# Main.net
KiCad netlist of a schematic drawn in Altium Designer
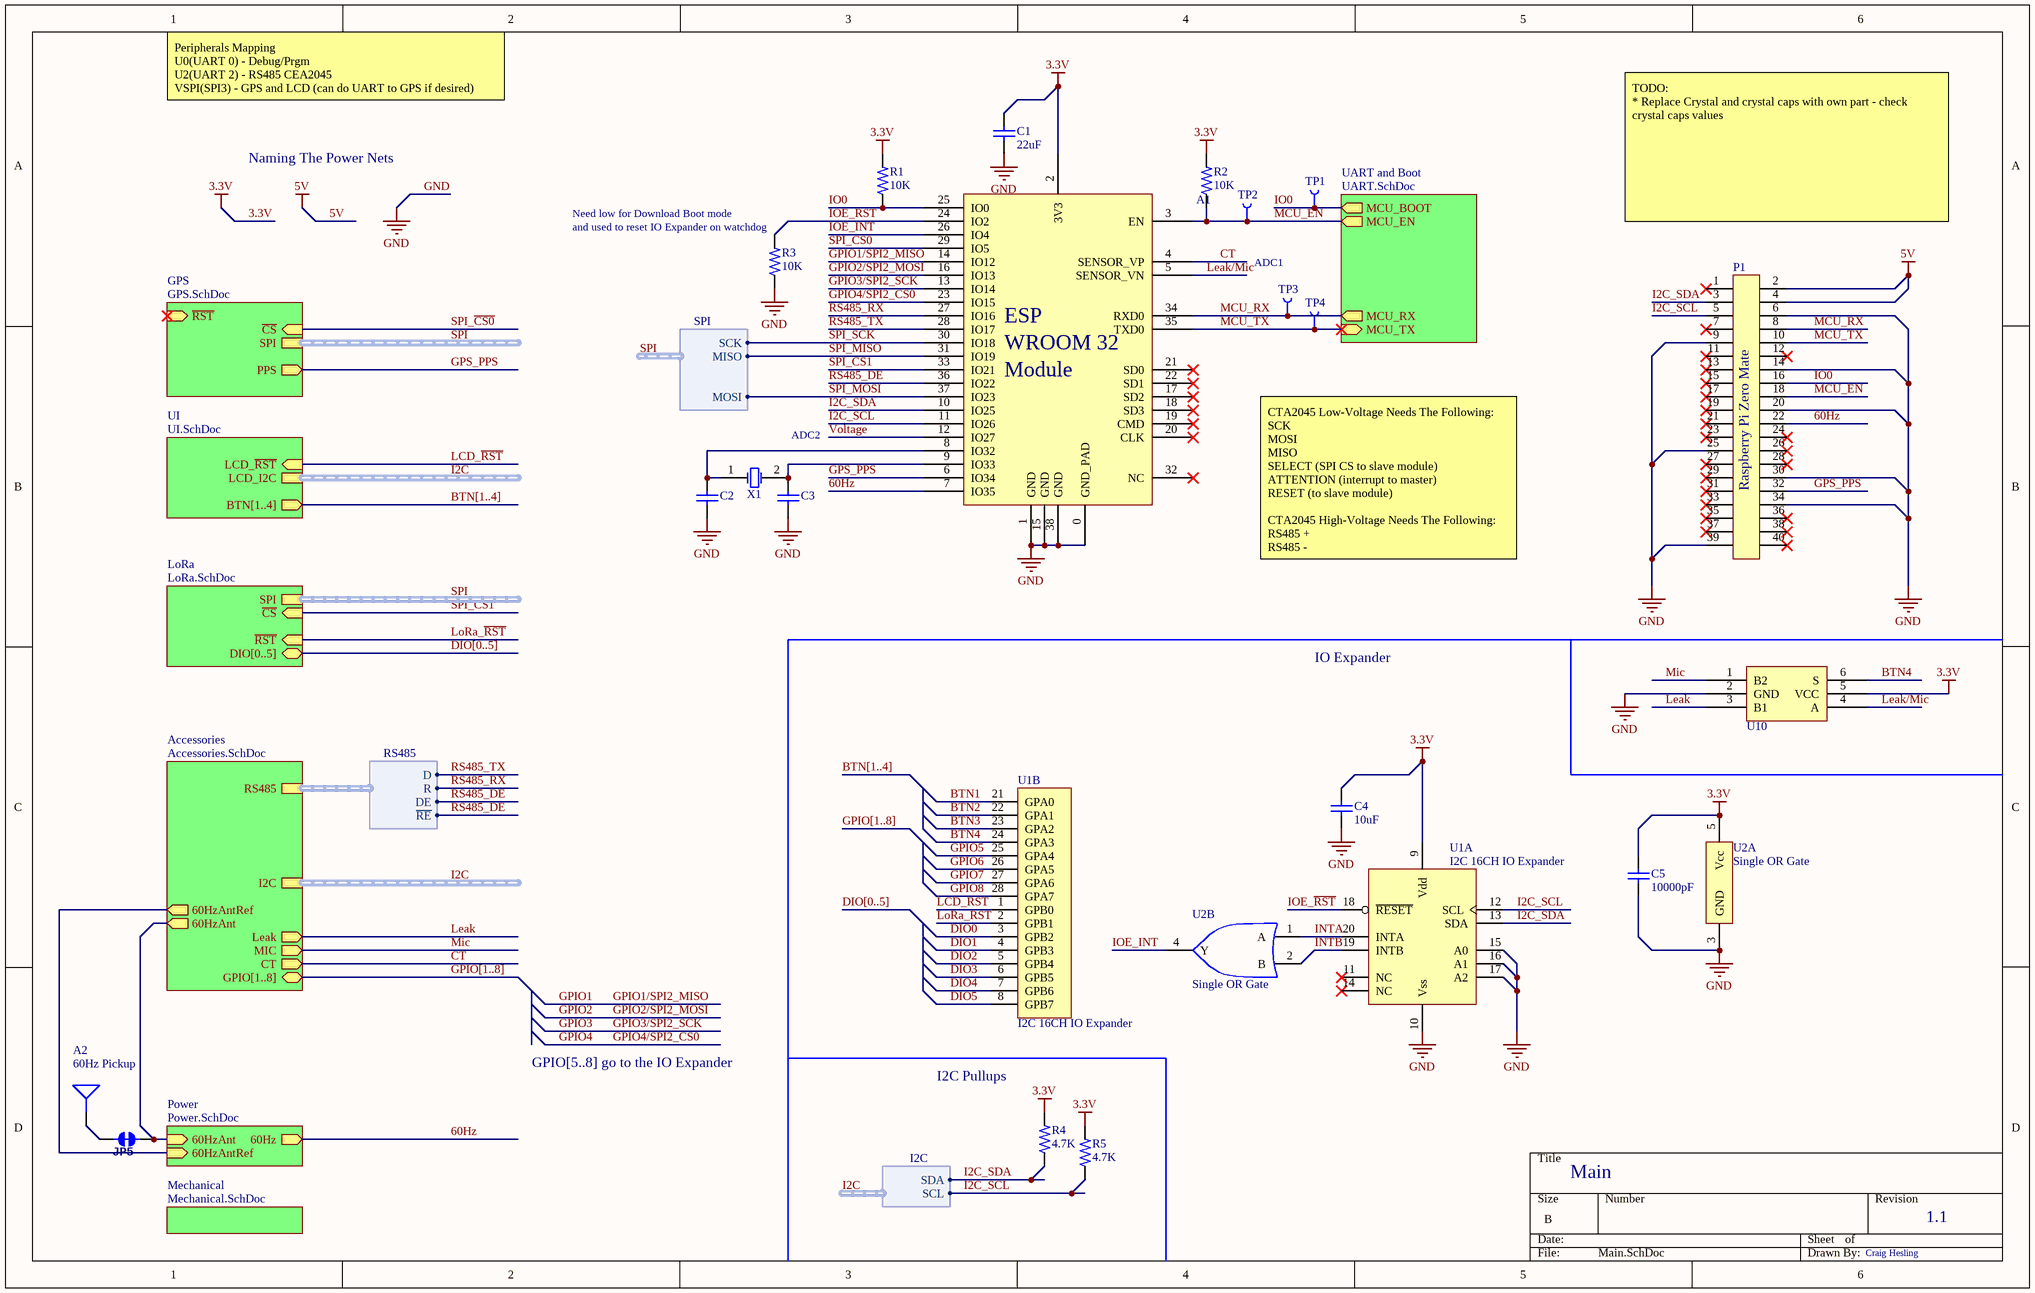
[diagram p0: Main.SchDoc]

(export (version "E")
  (design (tool "Eeschema 10.0.6"))
  (components
    (comp (ref "A1")
      (value "ESP-WROOM-32")
      (footprint "ESP-WROOM-32")
      (description "ESP WROOM 32 Module")
      (libsource (lib "Modules") (part "ESP-WROOM-32"))
    )
    (comp (ref "A2")
      (value "60Hz Pickup")
      (footprint "60HzPickup")
      (description "5cm 60Hz pickup antenna with via for external wire")
      (libsource (lib "Antennas") (part "60Hz pickup with via"))
    )
    (comp (ref "C1")
      (value "22uF")
      (footprint "CAPC2013X14L - CAP0805 1.45mm Tall")
      (description "SMT 0805 Ceramic Capacitor")
      (fields (field (name "TOLERANCE") "10%") (field (name "VOLTAGE") "6.3V"))
      (libsource (lib "Passives") (part "CAP0805 22uF 10% 6.3V X5R"))
    )
    (comp (ref "C2")
      (value "CAP 12pF 16V 0603(1608)")
      (footprint "CAPC0603(1608)100_M")
      (description "CAP 12pF 16V ±10% 0603 (1608 Metric) Thickness 1mm SMD")
      (fields (field (name "TOLERANCE") "Â±10%"))
      (libsource (lib "Altium Content Vault") (part "CAP"))
    )
    (comp (ref "C3")
      (value "CAP 12pF 16V 0603(1608)")
      (footprint "CAPC0603(1608)100_M")
      (description "CAP 12pF 16V ±10% 0603 (1608 Metric) Thickness 1mm SMD")
      (fields (field (name "TOLERANCE") "Â±10%"))
      (libsource (lib "Altium Content Vault") (part "CAP"))
    )
    (comp (ref "C4")
      (value "10uF")
      (footprint "CAPC2013X14L - CAP0805 1.45mm Tall")
      (description "SMT 0805 Ceramic Capacitor")
      (fields (field (name "TOLERANCE") "10%") (field (name "VOLTAGE") "6.3V"))
      (libsource (lib "Passives") (part "CAP0805 10uF 10% 6.3V X5R"))
    )
    (comp (ref "C5")
      (value "10000pF")
      (footprint "CAPC1608X09L - CAP0603")
      (description "SMT 0603 Ceramic Capacitor")
      (fields (field (name "TOLERANCE") "10%") (field (name "VOLTAGE") "50V"))
      (libsource (lib "Passives") (part "CAP0603 10000pF 10% 50V X7R"))
    )
    (comp (ref "JP5")
      (value "JUMPER-PAD-2-NC_BY_TRACENO_SILK")
      (footprint "PAD-JUMPER-2-NC_BY_TRACE_NO_SILK")
      (libsource (lib "Passives") (part "JUMPER-PAD-2-NC_BY_TRACENO_SILK"))
    )
    (comp (ref "P1")
      (value "Raspbery Pi Zero Mate")
      (footprint "Raspberry Pi Zero")
      (description "The header and mechanical drawings for connnecting a Raspbery Pi Zero")
      (libsource (lib "Misc") (part "Raspberry Pi Zero Mate"))
    )
    (comp (ref "R1")
      (value "10K")
      (footprint "RESC1608X06L - RES0603")
      (description "SMT 0603 Ceramic Resistor")
      (fields (field (name "POWER") "1/10W") (field (name "TOLERANCE") "1%"))
      (libsource (lib "Passives") (part "RES0603 10K 1% 1/10W"))
    )
    (comp (ref "R2")
      (value "10K")
      (footprint "RESC1608X06L - RES0603")
      (description "SMT 0603 Ceramic Resistor")
      (fields (field (name "POWER") "1/10W") (field (name "TOLERANCE") "1%"))
      (libsource (lib "Passives") (part "RES0603 10K 1% 1/10W"))
    )
    (comp (ref "R3")
      (value "10K")
      (footprint "RESC1608X06L - RES0603")
      (description "SMT 0603 Ceramic Resistor")
      (fields (field (name "POWER") "1/10W") (field (name "TOLERANCE") "1%"))
      (libsource (lib "Passives") (part "RES0603 10K 1% 1/10W"))
    )
    (comp (ref "R4")
      (value "4.7K")
      (footprint "RESC1608X06L - RES0603")
      (description "SMT 0603 Ceramic Resistor")
      (fields (field (name "POWER") "1/10W") (field (name "TOLERANCE") "1%"))
      (libsource (lib "Passives") (part "RES0603 4.7K 1% 1/10W"))
    )
    (comp (ref "R5")
      (value "4.7K")
      (footprint "RESC1608X06L - RES0603")
      (description "SMT 0603 Ceramic Resistor")
      (fields (field (name "POWER") "1/10W") (field (name "TOLERANCE") "1%"))
      (libsource (lib "Passives") (part "RES0603 4.7K 1% 1/10W"))
    )
    (comp (ref "TP1")
      (value "Test Point")
      (footprint "TestPoint1")
      (description "Small 0.762mm Round Test Point")
      (libsource (lib "Passives") (part "TestPoint1"))
    )
    (comp (ref "TP2")
      (value "Test Point")
      (footprint "TestPoint1")
      (description "Small 0.762mm Round Test Point")
      (libsource (lib "Passives") (part "TestPoint1"))
    )
    (comp (ref "TP3")
      (value "Test Point")
      (footprint "TestPoint1")
      (description "Small 0.762mm Round Test Point")
      (libsource (lib "Passives") (part "TestPoint1"))
    )
    (comp (ref "TP4")
      (value "Test Point")
      (footprint "TestPoint1")
      (description "Small 0.762mm Round Test Point")
      (libsource (lib "Passives") (part "TestPoint1"))
    )
    (comp (ref "U1")
      (value "I2C 16CH IO Expander")
      (footprint "SOIC127P1030X265-28L")
      (description "Microchip MCP23017 I2C 16CH IO Expander")
      (libsource (lib "Actives") (part "MCP23017T-E/SO"))
    )
    (comp (ref "U2")
      (value "Single OR Gate")
      (footprint "SOT95P280X140-5L")
      (description "Fairchild/ON Semi NC7S32M5X Single OR Gate")
      (libsource (lib "") (part "NC7S32M5X_1"))
    )
    (comp (ref "U10")
      (value "SN74LVC1G3157DCKR")
      (footprint "SC-70-6  (SOT-363)")
      (description "IC, SWITCH, SPDT ANA, SMD")
      (fields (field (name "MANUFACTURER") "Texas Instruments"))
      (libsource (lib "Actives") (part "SN74LVC1G3157DCKR"))
    )
    (comp (ref "X1")
      (value "14340272-32.768KHz")
      (footprint "ITTI-14340272-32.768KHz-2_V")
      (description "Crystal, 32.768 KHz, -40 to 85 degC, 3.2 x 1.5 x 0.9 mm SMD")
      (fields (field (name "MANUFACTURER") "ITTI"))
      (libsource (lib "Altium Content Vault") (part "ITTI-14340272-2"))
    )
  )
  (nets
    (net (code "6") (name "/60Hz") (class "Default")
      (node (ref "A1") (pin "7") (pinfunction "IO35_7") (pintype "passive"))
      (node (ref "P1") (pin "22") (pintype "passive"))
    )
    (net (code "7") (name "/60HzAnt") (class "Default")
      (node (ref "JP5") (pin "2") (pinfunction "2_2") (pintype "passive"))
    )
    (net (code "9") (name "/BTN1") (class "Default")
      (node (ref "U1") (pin "21") (pinfunction "GPA0_21") (pintype "passive"))
    )
    (net (code "10") (name "/BTN2") (class "Default")
      (node (ref "U1") (pin "22") (pinfunction "GPA1_22") (pintype "passive"))
    )
    (net (code "11") (name "/BTN3") (class "Default")
      (node (ref "U1") (pin "23") (pinfunction "GPA2_23") (pintype "passive"))
    )
    (net (code "12") (name "/BTN4") (class "Default")
      (node (ref "U1") (pin "24") (pinfunction "GPA3_24") (pintype "passive"))
      (node (ref "U10") (pin "6") (pinfunction "S_6") (pintype "passive"))
    )
    (net (code "14") (name "/CT") (class "Default")
      (node (ref "A1") (pin "4") (pinfunction "SENSOR_VP_4") (pintype "passive"))
    )
    (net (code "15") (name "/DIO0") (class "Default")
      (node (ref "U1") (pin "3") (pinfunction "GPB2_3") (pintype "passive"))
    )
    (net (code "16") (name "/DIO1") (class "Default")
      (node (ref "U1") (pin "4") (pinfunction "GPB3_4") (pintype "passive"))
    )
    (net (code "17") (name "/DIO2") (class "Default")
      (node (ref "U1") (pin "5") (pinfunction "GPB4_5") (pintype "passive"))
    )
    (net (code "18") (name "/DIO3") (class "Default")
      (node (ref "U1") (pin "6") (pinfunction "GPB5_6") (pintype "passive"))
    )
    (net (code "19") (name "/DIO4") (class "Default")
      (node (ref "U1") (pin "7") (pinfunction "GPB6_7") (pintype "passive"))
    )
    (net (code "20") (name "/DIO5") (class "Default")
      (node (ref "U1") (pin "8") (pinfunction "GPB7_8") (pintype "passive"))
    )
    (net (code "22") (name "/GPIO1") (class "Default")
      (node (ref "A1") (pin "14") (pinfunction "IO12_14") (pintype "passive"))
    )
    (net (code "23") (name "/GPIO2") (class "Default")
      (node (ref "A1") (pin "16") (pinfunction "IO13_16") (pintype "passive"))
    )
    (net (code "24") (name "/GPIO3") (class "Default")
      (node (ref "A1") (pin "13") (pinfunction "IO14_13") (pintype "passive"))
    )
    (net (code "25") (name "/GPIO4") (class "Default")
      (node (ref "A1") (pin "23") (pinfunction "IO15_23") (pintype "passive"))
    )
    (net (code "26") (name "/GPIO5") (class "Default")
      (node (ref "U1") (pin "25") (pinfunction "GPA4_25") (pintype "passive"))
    )
    (net (code "27") (name "/GPIO6") (class "Default")
      (node (ref "U1") (pin "26") (pinfunction "GPA5_26") (pintype "passive"))
    )
    (net (code "28") (name "/GPIO7") (class "Default")
      (node (ref "U1") (pin "27") (pinfunction "GPA6_27") (pintype "passive"))
    )
    (net (code "29") (name "/GPIO8") (class "Default")
      (node (ref "U1") (pin "28") (pinfunction "GPA7_28") (pintype "passive"))
    )
    (net (code "31") (name "/GPS_PPS") (class "Default")
      (node (ref "A1") (pin "6") (pinfunction "IO34_6") (pintype "passive"))
      (node (ref "P1") (pin "32") (pintype "passive"))
    )
    (net (code "32") (name "/I2C_SCL") (class "Default")
      (node (ref "A1") (pin "11") (pinfunction "IO26_11") (pintype "passive"))
      (node (ref "P1") (pin "5") (pintype "passive"))
      (node (ref "R5") (pin "1") (pinfunction "1_1") (pintype "passive"))
      (node (ref "U1") (pin "12") (pinfunction "SCL_12") (pintype "passive"))
    )
    (net (code "33") (name "/I2C_SDA") (class "Default")
      (node (ref "A1") (pin "10") (pinfunction "IO25_10") (pintype "passive"))
      (node (ref "P1") (pin "3") (pintype "passive"))
      (node (ref "R4") (pin "1") (pinfunction "1_1") (pintype "passive"))
      (node (ref "U1") (pin "13") (pinfunction "SDA_13") (pintype "passive"))
    )
    (net (code "35") (name "/INTA") (class "Default")
      (node (ref "U1") (pin "20") (pinfunction "INTA_20") (pintype "passive"))
      (node (ref "U2") (pin "1") (pinfunction "A_1") (pintype "passive"))
    )
    (net (code "36") (name "/INTB") (class "Default")
      (node (ref "U1") (pin "19") (pinfunction "INTB_19") (pintype "passive"))
      (node (ref "U2") (pin "2") (pinfunction "B_2") (pintype "passive"))
    )
    (net (code "37") (name "/IO0") (class "Default")
      (node (ref "A1") (pin "25") (pinfunction "IO0_25") (pintype "passive"))
      (node (ref "P1") (pin "16") (pintype "passive"))
      (node (ref "R1") (pin "1") (pinfunction "1_1") (pintype "passive"))
      (node (ref "TP1") (pin "1") (pinfunction "P1_1") (pintype "passive"))
    )
    (net (code "38") (name "/IOE_INT") (class "Default")
      (node (ref "A1") (pin "26") (pinfunction "IO4_26") (pintype "passive"))
      (node (ref "U2") (pin "4") (pinfunction "Y_4") (pintype "passive"))
    )
    (net (code "39") (name "/IOE_~{RST}") (class "Default")
      (node (ref "A1") (pin "24") (pinfunction "IO2_24") (pintype "passive"))
      (node (ref "R3") (pin "2") (pinfunction "2_2") (pintype "passive"))
      (node (ref "U1") (pin "18") (pinfunction "~{RESET}_18") (pintype "passive"))
    )
    (net (code "40") (name "/LCD_~{RST}") (class "Default")
      (node (ref "U1") (pin "1") (pinfunction "GPB0_1") (pintype "passive"))
    )
    (net (code "41") (name "/Leak") (class "Default")
      (node (ref "U10") (pin "3") (pinfunction "B1_3") (pintype "passive"))
    )
    (net (code "42") (name "/Leak{slash}Mic") (class "Default")
      (node (ref "A1") (pin "5") (pinfunction "SENSOR_VN_5") (pintype "passive"))
      (node (ref "U10") (pin "4") (pinfunction "A_4") (pintype "passive"))
    )
    (net (code "43") (name "/LoRa_~{RST}") (class "Default")
      (node (ref "U1") (pin "2") (pinfunction "GPB1_2") (pintype "passive"))
    )
    (net (code "44") (name "/MCU_EN") (class "Default")
      (node (ref "A1") (pin "3") (pinfunction "EN_3") (pintype "passive"))
      (node (ref "P1") (pin "18") (pintype "passive"))
      (node (ref "R2") (pin "1") (pinfunction "1_1") (pintype "passive"))
      (node (ref "TP2") (pin "1") (pinfunction "P1_1") (pintype "passive"))
    )
    (net (code "45") (name "/MCU_RX") (class "Default")
      (node (ref "A1") (pin "34") (pinfunction "RXD0_34") (pintype "passive"))
      (node (ref "P1") (pin "8") (pintype "passive"))
      (node (ref "TP3") (pin "1") (pinfunction "P1_1") (pintype "passive"))
    )
    (net (code "46") (name "/MCU_TX") (class "Default")
      (node (ref "A1") (pin "35") (pinfunction "TXD0_35") (pintype "passive"))
      (node (ref "P1") (pin "10") (pintype "passive"))
      (node (ref "TP4") (pin "1") (pinfunction "P1_1") (pintype "passive"))
    )
    (net (code "47") (name "/Mic") (class "Default")
      (node (ref "U10") (pin "1") (pinfunction "B2_1") (pintype "passive"))
    )
    (net (code "48") (name "/RS485_DE") (class "Default")
      (node (ref "A1") (pin "36") (pinfunction "IO22_36") (pintype "passive"))
    )
    (net (code "49") (name "/RS485_RX") (class "Default")
      (node (ref "A1") (pin "27") (pinfunction "IO16_27") (pintype "passive"))
    )
    (net (code "50") (name "/RS485_TX") (class "Default")
      (node (ref "A1") (pin "28") (pinfunction "IO17_28") (pintype "passive"))
    )
    (net (code "51") (name "/SPI_MISO") (class "Default")
      (node (ref "A1") (pin "31") (pinfunction "IO19_31") (pintype "passive"))
    )
    (net (code "52") (name "/SPI_MOSI") (class "Default")
      (node (ref "A1") (pin "37") (pinfunction "IO23_37") (pintype "passive"))
    )
    (net (code "53") (name "/SPI_SCK") (class "Default")
      (node (ref "A1") (pin "30") (pinfunction "IO18_30") (pintype "passive"))
    )
    (net (code "54") (name "/SPI_~{CS0}") (class "Default")
      (node (ref "A1") (pin "29") (pinfunction "IO5_29") (pintype "passive"))
    )
    (net (code "55") (name "/SPI_~{CS1}") (class "Default")
      (node (ref "A1") (pin "33") (pinfunction "IO21_33") (pintype "passive"))
    )
    (net (code "57") (name "/Voltage") (class "Default")
      (node (ref "A1") (pin "12") (pinfunction "IO27_12") (pintype "passive"))
    )
    (net (code "62") (name "3.3V") (class "Default")
      (node (ref "A1") (pin "2") (pinfunction "3V3_2") (pintype "power_in"))
      (node (ref "C1") (pin "2") (pinfunction "2_2") (pintype "passive"))
      (node (ref "C4") (pin "2") (pinfunction "2_2") (pintype "passive"))
      (node (ref "C5") (pin "2") (pinfunction "2_2") (pintype "passive"))
      (node (ref "R1") (pin "2") (pinfunction "2_2") (pintype "passive"))
      (node (ref "R2") (pin "2") (pinfunction "2_2") (pintype "passive"))
      (node (ref "R4") (pin "2") (pinfunction "2_2") (pintype "passive"))
      (node (ref "R5") (pin "2") (pinfunction "2_2") (pintype "passive"))
      (node (ref "U1") (pin "9") (pinfunction "Vdd_9") (pintype "passive"))
      (node (ref "U10") (pin "5") (pinfunction "VCC_5") (pintype "passive"))
      (node (ref "U2") (pin "5") (pinfunction "Vcc_5") (pintype "passive"))
    )
    (net (code "63") (name "5V") (class "Default")
      (node (ref "P1") (pin "2") (pintype "passive"))
      (node (ref "P1") (pin "4") (pintype "passive"))
    )
    (net (code "64") (name "GND") (class "Default")
      (node (ref "A1") (pin "0") (pinfunction "GND_PAD_0") (pintype "power_in"))
      (node (ref "A1") (pin "1") (pinfunction "GND_1") (pintype "power_in"))
      (node (ref "A1") (pin "15") (pinfunction "GND_15") (pintype "power_in"))
      (node (ref "A1") (pin "38") (pinfunction "GND_38") (pintype "power_in"))
      (node (ref "C1") (pin "1") (pinfunction "1_1") (pintype "passive"))
      (node (ref "C2") (pin "1") (pinfunction "1_1") (pintype "passive"))
      (node (ref "C3") (pin "1") (pinfunction "1_1") (pintype "passive"))
      (node (ref "C4") (pin "1") (pinfunction "1_1") (pintype "passive"))
      (node (ref "C5") (pin "1") (pinfunction "1_1") (pintype "passive"))
      (node (ref "P1") (pin "14") (pintype "passive"))
      (node (ref "P1") (pin "20") (pintype "passive"))
      (node (ref "P1") (pin "25") (pintype "passive"))
      (node (ref "P1") (pin "30") (pintype "passive"))
      (node (ref "P1") (pin "34") (pintype "passive"))
      (node (ref "P1") (pin "39") (pintype "passive"))
      (node (ref "P1") (pin "6") (pintype "passive"))
      (node (ref "P1") (pin "9") (pintype "passive"))
      (node (ref "R3") (pin "1") (pinfunction "1_1") (pintype "passive"))
      (node (ref "U1") (pin "10") (pinfunction "Vss_10") (pintype "passive"))
      (node (ref "U1") (pin "15") (pinfunction "A0_15") (pintype "passive"))
      (node (ref "U1") (pin "16") (pinfunction "A1_16") (pintype "passive"))
      (node (ref "U1") (pin "17") (pinfunction "A2_17") (pintype "passive"))
      (node (ref "U10") (pin "2") (pinfunction "GND_2") (pintype "passive"))
      (node (ref "U2") (pin "3") (pinfunction "GND_3") (pintype "passive"))
    )
    (net (code "65") (name "Net-(A1-IO32)") (class "Default")
      (node (ref "A1") (pin "8") (pinfunction "IO32_8") (pintype "passive"))
      (node (ref "C2") (pin "2") (pinfunction "2_2") (pintype "passive"))
      (node (ref "X1") (pin "1") (pinfunction "X1_1") (pintype "passive"))
    )
    (net (code "66") (name "Net-(A1-IO33)") (class "Default")
      (node (ref "A1") (pin "9") (pinfunction "IO33_9") (pintype "passive"))
      (node (ref "C3") (pin "2") (pinfunction "2_2") (pintype "passive"))
      (node (ref "X1") (pin "2") (pinfunction "X2_2") (pintype "passive"))
    )
    (net (code "67") (name "Net-(A2-Ant)") (class "Default")
      (node (ref "A2") (pin "1") (pinfunction "Ant_1") (pintype "passive"))
      (node (ref "JP5") (pin "1") (pinfunction "1_1") (pintype "passive"))
    )
    (net (code "68") (name "unconnected-(A1-CLK-Pad20)") (class "Default")
      (node (ref "A1") (pin "20") (pinfunction "CLK_20") (pintype "passive+no_connect"))
    )
    (net (code "69") (name "unconnected-(A1-CMD-Pad19)") (class "Default")
      (node (ref "A1") (pin "19") (pinfunction "CMD_19") (pintype "passive+no_connect"))
    )
    (net (code "70") (name "unconnected-(A1-NC-Pad32)") (class "Default")
      (node (ref "A1") (pin "32") (pinfunction "NC_32") (pintype "passive+no_connect"))
    )
    (net (code "71") (name "unconnected-(A1-SD0-Pad21)") (class "Default")
      (node (ref "A1") (pin "21") (pinfunction "SD0_21") (pintype "passive+no_connect"))
    )
    (net (code "72") (name "unconnected-(A1-SD1-Pad22)") (class "Default")
      (node (ref "A1") (pin "22") (pinfunction "SD1_22") (pintype "passive+no_connect"))
    )
    (net (code "73") (name "unconnected-(A1-SD2-Pad17)") (class "Default")
      (node (ref "A1") (pin "17") (pinfunction "SD2_17") (pintype "passive+no_connect"))
    )
    (net (code "74") (name "unconnected-(A1-SD3-Pad18)") (class "Default")
      (node (ref "A1") (pin "18") (pinfunction "SD3_18") (pintype "passive+no_connect"))
    )
    (net (code "75") (name "unconnected-(P1-Pad1)") (class "Default")
      (node (ref "P1") (pin "1") (pintype "passive+no_connect"))
    )
    (net (code "76") (name "unconnected-(P1-Pad7)") (class "Default")
      (node (ref "P1") (pin "7") (pintype "passive+no_connect"))
    )
    (net (code "77") (name "unconnected-(P1-Pad11)") (class "Default")
      (node (ref "P1") (pin "11") (pintype "passive+no_connect"))
    )
    (net (code "78") (name "unconnected-(P1-Pad12)") (class "Default")
      (node (ref "P1") (pin "12") (pintype "passive+no_connect"))
    )
    (net (code "79") (name "unconnected-(P1-Pad13)") (class "Default")
      (node (ref "P1") (pin "13") (pintype "passive+no_connect"))
    )
    (net (code "80") (name "unconnected-(P1-Pad15)") (class "Default")
      (node (ref "P1") (pin "15") (pintype "passive+no_connect"))
    )
    (net (code "81") (name "unconnected-(P1-Pad17)") (class "Default")
      (node (ref "P1") (pin "17") (pintype "passive+no_connect"))
    )
    (net (code "82") (name "unconnected-(P1-Pad19)") (class "Default")
      (node (ref "P1") (pin "19") (pintype "passive+no_connect"))
    )
    (net (code "83") (name "unconnected-(P1-Pad21)") (class "Default")
      (node (ref "P1") (pin "21") (pintype "passive+no_connect"))
    )
    (net (code "84") (name "unconnected-(P1-Pad23)") (class "Default")
      (node (ref "P1") (pin "23") (pintype "passive+no_connect"))
    )
    (net (code "85") (name "unconnected-(P1-Pad24)") (class "Default")
      (node (ref "P1") (pin "24") (pintype "passive+no_connect"))
    )
    (net (code "86") (name "unconnected-(P1-Pad26)") (class "Default")
      (node (ref "P1") (pin "26") (pintype "passive+no_connect"))
    )
    (net (code "87") (name "unconnected-(P1-Pad27)") (class "Default")
      (node (ref "P1") (pin "27") (pintype "passive+no_connect"))
    )
    (net (code "88") (name "unconnected-(P1-Pad28)") (class "Default")
      (node (ref "P1") (pin "28") (pintype "passive+no_connect"))
    )
    (net (code "89") (name "unconnected-(P1-Pad29)") (class "Default")
      (node (ref "P1") (pin "29") (pintype "passive+no_connect"))
    )
    (net (code "90") (name "unconnected-(P1-Pad31)") (class "Default")
      (node (ref "P1") (pin "31") (pintype "passive+no_connect"))
    )
    (net (code "91") (name "unconnected-(P1-Pad33)") (class "Default")
      (node (ref "P1") (pin "33") (pintype "passive+no_connect"))
    )
    (net (code "92") (name "unconnected-(P1-Pad35)") (class "Default")
      (node (ref "P1") (pin "35") (pintype "passive+no_connect"))
    )
    (net (code "93") (name "unconnected-(P1-Pad36)") (class "Default")
      (node (ref "P1") (pin "36") (pintype "passive+no_connect"))
    )
    (net (code "94") (name "unconnected-(P1-Pad37)") (class "Default")
      (node (ref "P1") (pin "37") (pintype "passive+no_connect"))
    )
    (net (code "95") (name "unconnected-(P1-Pad38)") (class "Default")
      (node (ref "P1") (pin "38") (pintype "passive+no_connect"))
    )
    (net (code "96") (name "unconnected-(P1-Pad40)") (class "Default")
      (node (ref "P1") (pin "40") (pintype "passive+no_connect"))
    )
    (net (code "97") (name "unconnected-(U1A-NC-Pad11)") (class "Default")
      (node (ref "U1") (pin "11") (pinfunction "NC_11") (pintype "passive+no_connect"))
    )
    (net (code "98") (name "unconnected-(U1A-NC-Pad14)") (class "Default")
      (node (ref "U1") (pin "14") (pinfunction "NC_14") (pintype "passive+no_connect"))
    )
  )
)
